# psg-dual-ad9833-simp.net
KiCad netlist of a schematic drawn in EAGLE
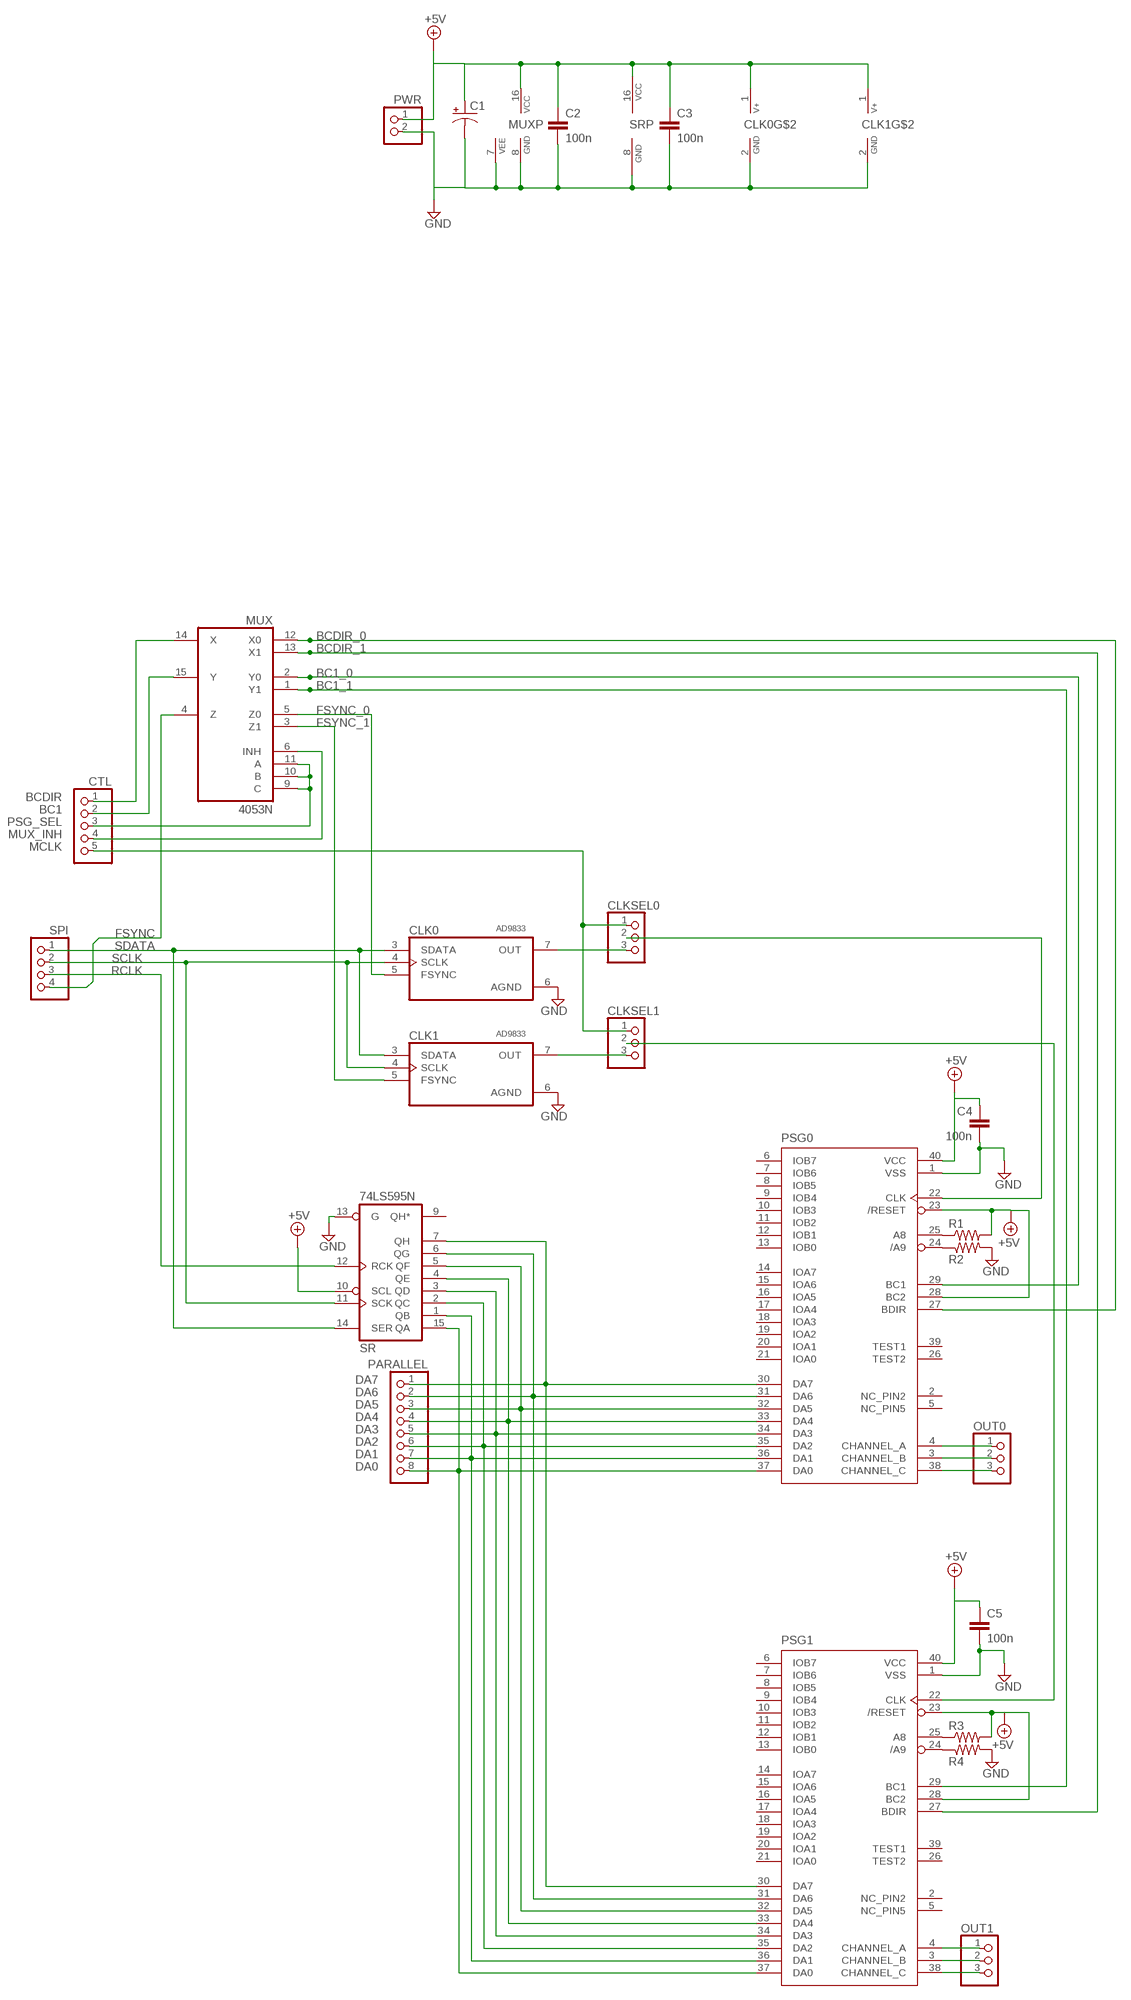
[diagram p0: schematic, sheet 1]

(export (version "E")
  (design (tool "Eeschema 10.0.6"))
  (components
    (comp (ref "C1")
      (value "0501")
      (footprint "eagle-import:050_020_1")
      (libsource (lib "eagle-import") (part "0501"))
    )
    (comp (ref "C2")
      (value "100n")
      (footprint "eagle-import:050X030_025")
      (libsource (lib "eagle-import") (part "050X030_0251"))
    )
    (comp (ref "C3")
      (value "100n")
      (footprint "eagle-import:050X030_025")
      (libsource (lib "eagle-import") (part "050X030_0251"))
    )
    (comp (ref "C4")
      (value "100n")
      (footprint "eagle-import:050X030_025_3")
      (libsource (lib "eagle-import") (part "050X030_0253"))
    )
    (comp (ref "C5")
      (value "100n")
      (footprint "eagle-import:050X030_025_3")
      (libsource (lib "eagle-import") (part "050X030_0253"))
    )
    (comp (ref "CLK0")
      (value "AD9833_MODULE")
      (footprint "eagle-import:AD9833_MODULE")
      (libsource (lib "eagle-import") (part "AD9833_MODULE"))
    )
    (comp (ref "CLK1")
      (value "AD9833_MODULE")
      (footprint "eagle-import:AD9833_MODULE")
      (libsource (lib "eagle-import") (part "AD9833_MODULE"))
    )
    (comp (ref "CLKSEL0")
      (value "PINHD-1X3/90")
      (footprint "eagle-import:1X03_90")
      (libsource (lib "eagle-import") (part "PINHD-1X3/90"))
    )
    (comp (ref "CLKSEL1")
      (value "PINHD-1X3/90")
      (footprint "eagle-import:1X03_90")
      (libsource (lib "eagle-import") (part "PINHD-1X3/90"))
    )
    (comp (ref "CTL")
      (value "PINHD-1X5/90")
      (footprint "eagle-import:1X05_90")
      (libsource (lib "eagle-import") (part "PINHD-1X5/90"))
    )
    (comp (ref "MUX")
      (value "4053N")
      (footprint "eagle-import:DIL16")
      (libsource (lib "eagle-import") (part "4053N"))
    )
    (comp (ref "OUT0")
      (value "PINHD-1X3/90")
      (footprint "eagle-import:1X03_90")
      (libsource (lib "eagle-import") (part "PINHD-1X3/90"))
    )
    (comp (ref "OUT1")
      (value "PINHD-1X3/90")
      (footprint "eagle-import:1X03_90")
      (libsource (lib "eagle-import") (part "PINHD-1X3/90"))
    )
    (comp (ref "PARALLEL")
      (value "PINHD-1X8/90")
      (footprint "eagle-import:1X08_90")
      (libsource (lib "eagle-import") (part "PINHD-1X8/90"))
    )
    (comp (ref "PSG0")
      (value "AY-3-8910")
      (footprint "eagle-import:DIL40")
      (libsource (lib "eagle-import") (part "AY-3-8910"))
    )
    (comp (ref "PSG1")
      (value "AY-3-8910")
      (footprint "eagle-import:DIL40")
      (libsource (lib "eagle-import") (part "AY-3-8910"))
    )
    (comp (ref "PWR")
      (value "PINHD-1X2/90")
      (footprint "eagle-import:1X02_90")
      (libsource (lib "eagle-import") (part "PINHD-1X2/90"))
    )
    (comp (ref "R1")
      (value "6MM.3")
      (footprint "eagle-import:R0207_3")
      (libsource (lib "eagle-import") (part "6MM.3"))
    )
    (comp (ref "R2")
      (value "6MM.3")
      (footprint "eagle-import:R0207_3")
      (libsource (lib "eagle-import") (part "6MM.3"))
    )
    (comp (ref "R3")
      (value "6MM.3")
      (footprint "eagle-import:R0207_3")
      (libsource (lib "eagle-import") (part "6MM.3"))
    )
    (comp (ref "R4")
      (value "6MM.3")
      (footprint "eagle-import:R0207_3")
      (libsource (lib "eagle-import") (part "6MM.3"))
    )
    (comp (ref "SPI")
      (value "PINHD-1X4/90")
      (footprint "eagle-import:1X04_90")
      (libsource (lib "eagle-import") (part "PINHD-1X4/90"))
    )
    (comp (ref "SR")
      (value "74LS595N")
      (footprint "eagle-import:DIL16")
      (libsource (lib "eagle-import") (part "74595NLS"))
    )
  )
  (nets
    (net (code "1") (name "+5V") (class "Default")
      (node (ref "C1") (pin "+") (pinfunction "+_+") (pintype "passive"))
      (node (ref "C2") (pin "1") (pinfunction "1_1") (pintype "passive"))
      (node (ref "C3") (pin "1") (pinfunction "1_1") (pintype "passive"))
      (node (ref "C4") (pin "1") (pinfunction "1_1") (pintype "passive"))
      (node (ref "C5") (pin "1") (pinfunction "1_1") (pintype "passive"))
      (node (ref "CLK0") (pin "1") (pinfunction "+V_1") (pintype "power_in"))
      (node (ref "CLK1") (pin "1") (pinfunction "+V_1") (pintype "power_in"))
      (node (ref "MUX") (pin "16") (pinfunction "VCC_16") (pintype "power_in"))
      (node (ref "PSG0") (pin "23") (pinfunction "/RESET_23") (pintype "input"))
      (node (ref "PSG0") (pin "28") (pinfunction "BC2_28") (pintype "input"))
      (node (ref "PSG0") (pin "40") (pinfunction "VCC_40") (pintype "power_in"))
      (node (ref "PSG1") (pin "23") (pinfunction "/RESET_23") (pintype "input"))
      (node (ref "PSG1") (pin "28") (pinfunction "BC2_28") (pintype "input"))
      (node (ref "PSG1") (pin "40") (pinfunction "VCC_40") (pintype "power_in"))
      (node (ref "PWR") (pin "1") (pinfunction "1_1") (pintype "passive"))
      (node (ref "R1") (pin "2") (pinfunction "2_2") (pintype "passive"))
      (node (ref "R3") (pin "2") (pinfunction "2_2") (pintype "passive"))
      (node (ref "SR") (pin "10") (pinfunction "SCL_10") (pintype "input"))
      (node (ref "SR") (pin "16") (pinfunction "VCC_16") (pintype "power_in"))
    )
    (net (code "2") (name "/BC1") (class "Default")
      (node (ref "CTL") (pin "2") (pinfunction "2_2") (pintype "passive"))
      (node (ref "MUX") (pin "15") (pinfunction "Y_15") (pintype "bidirectional"))
    )
    (net (code "3") (name "/BC1_0") (class "Default")
      (node (ref "MUX") (pin "2") (pinfunction "Y0_2") (pintype "bidirectional"))
      (node (ref "PSG0") (pin "29") (pinfunction "BC1_29") (pintype "input"))
    )
    (net (code "4") (name "/BC1_1") (class "Default")
      (node (ref "MUX") (pin "1") (pinfunction "Y1_1") (pintype "bidirectional"))
      (node (ref "PSG1") (pin "29") (pinfunction "BC1_29") (pintype "input"))
    )
    (net (code "5") (name "/BCDIR") (class "Default")
      (node (ref "CTL") (pin "1") (pinfunction "1_1") (pintype "passive"))
      (node (ref "MUX") (pin "14") (pinfunction "X_14") (pintype "bidirectional"))
    )
    (net (code "6") (name "/BCDIR_0") (class "Default")
      (node (ref "MUX") (pin "12") (pinfunction "X0_12") (pintype "bidirectional"))
      (node (ref "PSG0") (pin "27") (pinfunction "BDIR_27") (pintype "input"))
    )
    (net (code "7") (name "/BCDIR_1") (class "Default")
      (node (ref "MUX") (pin "13") (pinfunction "X1_13") (pintype "bidirectional"))
      (node (ref "PSG1") (pin "27") (pinfunction "BDIR_27") (pintype "input"))
    )
    (net (code "8") (name "/DA0") (class "Default")
      (node (ref "PARALLEL") (pin "8") (pinfunction "8_8") (pintype "passive"))
      (node (ref "PSG0") (pin "37") (pinfunction "DA0_37") (pintype "bidirectional"))
      (node (ref "PSG1") (pin "37") (pinfunction "DA0_37") (pintype "bidirectional"))
      (node (ref "SR") (pin "15") (pinfunction "QA_15") (pintype "tri_state"))
    )
    (net (code "9") (name "/DA1") (class "Default")
      (node (ref "PARALLEL") (pin "7") (pinfunction "7_7") (pintype "passive"))
      (node (ref "PSG0") (pin "36") (pinfunction "DA1_36") (pintype "bidirectional"))
      (node (ref "PSG1") (pin "36") (pinfunction "DA1_36") (pintype "bidirectional"))
      (node (ref "SR") (pin "1") (pinfunction "QB_1") (pintype "tri_state"))
    )
    (net (code "10") (name "/DA2") (class "Default")
      (node (ref "PARALLEL") (pin "6") (pinfunction "6_6") (pintype "passive"))
      (node (ref "PSG0") (pin "35") (pinfunction "DA2_35") (pintype "bidirectional"))
      (node (ref "PSG1") (pin "35") (pinfunction "DA2_35") (pintype "bidirectional"))
      (node (ref "SR") (pin "2") (pinfunction "QC_2") (pintype "tri_state"))
    )
    (net (code "11") (name "/DA3") (class "Default")
      (node (ref "PARALLEL") (pin "5") (pinfunction "5_5") (pintype "passive"))
      (node (ref "PSG0") (pin "34") (pinfunction "DA3_34") (pintype "bidirectional"))
      (node (ref "PSG1") (pin "34") (pinfunction "DA3_34") (pintype "bidirectional"))
      (node (ref "SR") (pin "3") (pinfunction "QD_3") (pintype "tri_state"))
    )
    (net (code "12") (name "/DA4") (class "Default")
      (node (ref "PARALLEL") (pin "4") (pinfunction "4_4") (pintype "passive"))
      (node (ref "PSG0") (pin "33") (pinfunction "DA4_33") (pintype "bidirectional"))
      (node (ref "PSG1") (pin "33") (pinfunction "DA4_33") (pintype "bidirectional"))
      (node (ref "SR") (pin "4") (pinfunction "QE_4") (pintype "tri_state"))
    )
    (net (code "13") (name "/DA5") (class "Default")
      (node (ref "PARALLEL") (pin "3") (pinfunction "3_3") (pintype "passive"))
      (node (ref "PSG0") (pin "32") (pinfunction "DA5_32") (pintype "bidirectional"))
      (node (ref "PSG1") (pin "32") (pinfunction "DA5_32") (pintype "bidirectional"))
      (node (ref "SR") (pin "5") (pinfunction "QF_5") (pintype "tri_state"))
    )
    (net (code "14") (name "/DA6") (class "Default")
      (node (ref "PARALLEL") (pin "2") (pinfunction "2_2") (pintype "passive"))
      (node (ref "PSG0") (pin "31") (pinfunction "DA6_31") (pintype "bidirectional"))
      (node (ref "PSG1") (pin "31") (pinfunction "DA6_31") (pintype "bidirectional"))
      (node (ref "SR") (pin "6") (pinfunction "QG_6") (pintype "tri_state"))
    )
    (net (code "15") (name "/DA7") (class "Default")
      (node (ref "PARALLEL") (pin "1") (pinfunction "1_1") (pintype "passive"))
      (node (ref "PSG0") (pin "30") (pinfunction "DA7_30") (pintype "bidirectional"))
      (node (ref "PSG1") (pin "30") (pinfunction "DA7_30") (pintype "bidirectional"))
      (node (ref "SR") (pin "7") (pinfunction "QH_7") (pintype "tri_state"))
    )
    (net (code "16") (name "/FSYNC") (class "Default")
      (node (ref "MUX") (pin "4") (pinfunction "Z_4") (pintype "bidirectional"))
      (node (ref "SPI") (pin "4") (pinfunction "4_4") (pintype "passive"))
    )
    (net (code "17") (name "/FSYNC_0") (class "Default")
      (node (ref "CLK0") (pin "5") (pinfunction "FSYNC_5") (pintype "input"))
      (node (ref "MUX") (pin "5") (pinfunction "Z0_5") (pintype "bidirectional"))
    )
    (net (code "18") (name "/FSYNC_1") (class "Default")
      (node (ref "CLK1") (pin "5") (pinfunction "FSYNC_5") (pintype "input"))
      (node (ref "MUX") (pin "3") (pinfunction "Z1_3") (pintype "bidirectional"))
    )
    (net (code "19") (name "/MCLK") (class "Default")
      (node (ref "CLKSEL0") (pin "1") (pinfunction "1_1") (pintype "passive"))
      (node (ref "CLKSEL1") (pin "1") (pinfunction "1_1") (pintype "passive"))
      (node (ref "CTL") (pin "5") (pinfunction "5_5") (pintype "passive"))
    )
    (net (code "20") (name "/MUX_INH") (class "Default")
      (node (ref "CTL") (pin "4") (pinfunction "4_4") (pintype "passive"))
      (node (ref "MUX") (pin "6") (pinfunction "INH_6") (pintype "input"))
    )
    (net (code "21") (name "/PSG_SEL") (class "Default")
      (node (ref "CTL") (pin "3") (pinfunction "3_3") (pintype "passive"))
      (node (ref "MUX") (pin "10") (pinfunction "B_10") (pintype "input"))
      (node (ref "MUX") (pin "11") (pinfunction "A_11") (pintype "input"))
      (node (ref "MUX") (pin "9") (pinfunction "C_9") (pintype "input"))
    )
    (net (code "22") (name "/RCLK") (class "Default")
      (node (ref "SPI") (pin "3") (pinfunction "3_3") (pintype "passive"))
      (node (ref "SR") (pin "12") (pinfunction "RCK_12") (pintype "input"))
    )
    (net (code "23") (name "/SCLK") (class "Default")
      (node (ref "CLK0") (pin "4") (pinfunction "SCLK_4") (pintype "input"))
      (node (ref "CLK1") (pin "4") (pinfunction "SCLK_4") (pintype "input"))
      (node (ref "SPI") (pin "2") (pinfunction "2_2") (pintype "passive"))
      (node (ref "SR") (pin "11") (pinfunction "SCK_11") (pintype "input"))
    )
    (net (code "24") (name "/SDATA") (class "Default")
      (node (ref "CLK0") (pin "3") (pinfunction "SDATA_3") (pintype "bidirectional"))
      (node (ref "CLK1") (pin "3") (pinfunction "SDATA_3") (pintype "bidirectional"))
      (node (ref "SPI") (pin "1") (pinfunction "1_1") (pintype "passive"))
      (node (ref "SR") (pin "14") (pinfunction "SER_14") (pintype "input"))
    )
    (net (code "25") (name "GND") (class "Default")
      (node (ref "C1") (pin "-") (pinfunction "-_-") (pintype "passive"))
      (node (ref "C2") (pin "2") (pinfunction "2_2") (pintype "passive"))
      (node (ref "C3") (pin "2") (pinfunction "2_2") (pintype "passive"))
      (node (ref "C4") (pin "2") (pinfunction "2_2") (pintype "passive"))
      (node (ref "C5") (pin "2") (pinfunction "2_2") (pintype "passive"))
      (node (ref "CLK0") (pin "2") (pinfunction "GND_2") (pintype "power_in"))
      (node (ref "CLK0") (pin "6") (pinfunction "AGND_6") (pintype "power_in"))
      (node (ref "CLK1") (pin "2") (pinfunction "GND_2") (pintype "power_in"))
      (node (ref "CLK1") (pin "6") (pinfunction "AGND_6") (pintype "power_in"))
      (node (ref "MUX") (pin "7") (pinfunction "VEE_7") (pintype "power_in"))
      (node (ref "MUX") (pin "8") (pinfunction "GND_8") (pintype "power_in"))
      (node (ref "PSG0") (pin "1") (pinfunction "VSS_1") (pintype "power_in"))
      (node (ref "PSG1") (pin "1") (pinfunction "VSS_1") (pintype "power_in"))
      (node (ref "PWR") (pin "2") (pinfunction "2_2") (pintype "passive"))
      (node (ref "R2") (pin "2") (pinfunction "2_2") (pintype "passive"))
      (node (ref "R4") (pin "2") (pinfunction "2_2") (pintype "passive"))
      (node (ref "SR") (pin "13") (pinfunction "G_13") (pintype "input"))
      (node (ref "SR") (pin "8") (pinfunction "GND_8") (pintype "power_in"))
    )
    (net (code "26") (name "Net-(CLK0A-OUT)") (class "Default")
      (node (ref "CLK0") (pin "7") (pinfunction "OUT_7") (pintype "output"))
      (node (ref "CLKSEL0") (pin "3") (pinfunction "3_3") (pintype "passive"))
    )
    (net (code "27") (name "Net-(CLK1A-OUT)") (class "Default")
      (node (ref "CLK1") (pin "7") (pinfunction "OUT_7") (pintype "output"))
      (node (ref "CLKSEL1") (pin "3") (pinfunction "3_3") (pintype "passive"))
    )
    (net (code "28") (name "Net-(PSG0-A8)") (class "Default")
      (node (ref "PSG0") (pin "25") (pinfunction "A8_25") (pintype "bidirectional"))
      (node (ref "R1") (pin "1") (pinfunction "1_1") (pintype "passive"))
    )
    (net (code "29") (name "Net-(PSG0-CHANNEL_A)") (class "Default")
      (node (ref "OUT0") (pin "1") (pinfunction "1_1") (pintype "passive"))
      (node (ref "PSG0") (pin "4") (pinfunction "CHANNEL_A_4") (pintype "output"))
    )
    (net (code "30") (name "Net-(PSG0-CHANNEL_B)") (class "Default")
      (node (ref "OUT0") (pin "2") (pinfunction "2_2") (pintype "passive"))
      (node (ref "PSG0") (pin "3") (pinfunction "CHANNEL_B_3") (pintype "output"))
    )
    (net (code "31") (name "Net-(PSG0-CHANNEL_C)") (class "Default")
      (node (ref "OUT0") (pin "3") (pinfunction "3_3") (pintype "passive"))
      (node (ref "PSG0") (pin "38") (pinfunction "CHANNEL_C_38") (pintype "output"))
    )
    (net (code "32") (name "Net-(PSG0-CLK)") (class "Default")
      (node (ref "CLKSEL0") (pin "2") (pinfunction "2_2") (pintype "passive"))
      (node (ref "PSG0") (pin "22") (pinfunction "CLK_22") (pintype "input"))
    )
    (net (code "33") (name "Net-(PSG0-{slash}A9)") (class "Default")
      (node (ref "PSG0") (pin "24") (pinfunction "/A9_24") (pintype "bidirectional"))
      (node (ref "R2") (pin "1") (pinfunction "1_1") (pintype "passive"))
    )
    (net (code "34") (name "Net-(PSG1-A8)") (class "Default")
      (node (ref "PSG1") (pin "25") (pinfunction "A8_25") (pintype "bidirectional"))
      (node (ref "R3") (pin "1") (pinfunction "1_1") (pintype "passive"))
    )
    (net (code "35") (name "Net-(PSG1-CHANNEL_A)") (class "Default")
      (node (ref "OUT1") (pin "1") (pinfunction "1_1") (pintype "passive"))
      (node (ref "PSG1") (pin "4") (pinfunction "CHANNEL_A_4") (pintype "output"))
    )
    (net (code "36") (name "Net-(PSG1-CHANNEL_B)") (class "Default")
      (node (ref "OUT1") (pin "2") (pinfunction "2_2") (pintype "passive"))
      (node (ref "PSG1") (pin "3") (pinfunction "CHANNEL_B_3") (pintype "output"))
    )
    (net (code "37") (name "Net-(PSG1-CHANNEL_C)") (class "Default")
      (node (ref "OUT1") (pin "3") (pinfunction "3_3") (pintype "passive"))
      (node (ref "PSG1") (pin "38") (pinfunction "CHANNEL_C_38") (pintype "output"))
    )
    (net (code "38") (name "Net-(PSG1-CLK)") (class "Default")
      (node (ref "CLKSEL1") (pin "2") (pinfunction "2_2") (pintype "passive"))
      (node (ref "PSG1") (pin "22") (pinfunction "CLK_22") (pintype "input"))
    )
    (net (code "39") (name "Net-(PSG1-{slash}A9)") (class "Default")
      (node (ref "PSG1") (pin "24") (pinfunction "/A9_24") (pintype "bidirectional"))
      (node (ref "R4") (pin "1") (pinfunction "1_1") (pintype "passive"))
    )
    (net (code "40") (name "unconnected-(PSG0-IOA0-Pad21)") (class "Default")
      (node (ref "PSG0") (pin "21") (pinfunction "IOA0_21") (pintype "bidirectional"))
    )
    (net (code "41") (name "unconnected-(PSG0-IOA1-Pad20)") (class "Default")
      (node (ref "PSG0") (pin "20") (pinfunction "IOA1_20") (pintype "bidirectional"))
    )
    (net (code "42") (name "unconnected-(PSG0-IOA2-Pad19)") (class "Default")
      (node (ref "PSG0") (pin "19") (pinfunction "IOA2_19") (pintype "bidirectional"))
    )
    (net (code "43") (name "unconnected-(PSG0-IOA3-Pad18)") (class "Default")
      (node (ref "PSG0") (pin "18") (pinfunction "IOA3_18") (pintype "bidirectional"))
    )
    (net (code "44") (name "unconnected-(PSG0-IOA4-Pad17)") (class "Default")
      (node (ref "PSG0") (pin "17") (pinfunction "IOA4_17") (pintype "bidirectional"))
    )
    (net (code "45") (name "unconnected-(PSG0-IOA5-Pad16)") (class "Default")
      (node (ref "PSG0") (pin "16") (pinfunction "IOA5_16") (pintype "bidirectional"))
    )
    (net (code "46") (name "unconnected-(PSG0-IOA6-Pad15)") (class "Default")
      (node (ref "PSG0") (pin "15") (pinfunction "IOA6_15") (pintype "bidirectional"))
    )
    (net (code "47") (name "unconnected-(PSG0-IOA7-Pad14)") (class "Default")
      (node (ref "PSG0") (pin "14") (pinfunction "IOA7_14") (pintype "bidirectional"))
    )
    (net (code "48") (name "unconnected-(PSG0-IOB0-Pad13)") (class "Default")
      (node (ref "PSG0") (pin "13") (pinfunction "IOB0_13") (pintype "bidirectional"))
    )
    (net (code "49") (name "unconnected-(PSG0-IOB1-Pad12)") (class "Default")
      (node (ref "PSG0") (pin "12") (pinfunction "IOB1_12") (pintype "bidirectional"))
    )
    (net (code "50") (name "unconnected-(PSG0-IOB2-Pad11)") (class "Default")
      (node (ref "PSG0") (pin "11") (pinfunction "IOB2_11") (pintype "bidirectional"))
    )
    (net (code "51") (name "unconnected-(PSG0-IOB3-Pad10)") (class "Default")
      (node (ref "PSG0") (pin "10") (pinfunction "IOB3_10") (pintype "bidirectional"))
    )
    (net (code "52") (name "unconnected-(PSG0-IOB4-Pad9)") (class "Default")
      (node (ref "PSG0") (pin "9") (pinfunction "IOB4_9") (pintype "bidirectional"))
    )
    (net (code "53") (name "unconnected-(PSG0-IOB5-Pad8)") (class "Default")
      (node (ref "PSG0") (pin "8") (pinfunction "IOB5_8") (pintype "bidirectional"))
    )
    (net (code "54") (name "unconnected-(PSG0-IOB6-Pad7)") (class "Default")
      (node (ref "PSG0") (pin "7") (pinfunction "IOB6_7") (pintype "bidirectional"))
    )
    (net (code "55") (name "unconnected-(PSG0-IOB7-Pad6)") (class "Default")
      (node (ref "PSG0") (pin "6") (pinfunction "IOB7_6") (pintype "bidirectional"))
    )
    (net (code "56") (name "unconnected-(PSG0-NC_PIN2-Pad2)") (class "Default")
      (node (ref "PSG0") (pin "2") (pinfunction "NC_PIN2_2") (pintype "no_connect"))
    )
    (net (code "57") (name "unconnected-(PSG0-NC_PIN5-Pad5)") (class "Default")
      (node (ref "PSG0") (pin "5") (pinfunction "NC_PIN5_5") (pintype "bidirectional"))
    )
    (net (code "58") (name "unconnected-(PSG0-TEST1-Pad39)") (class "Default")
      (node (ref "PSG0") (pin "39") (pinfunction "TEST1_39") (pintype "no_connect"))
    )
    (net (code "59") (name "unconnected-(PSG0-TEST2-Pad26)") (class "Default")
      (node (ref "PSG0") (pin "26") (pinfunction "TEST2_26") (pintype "no_connect"))
    )
    (net (code "60") (name "unconnected-(PSG1-IOA0-Pad21)") (class "Default")
      (node (ref "PSG1") (pin "21") (pinfunction "IOA0_21") (pintype "bidirectional"))
    )
    (net (code "61") (name "unconnected-(PSG1-IOA1-Pad20)") (class "Default")
      (node (ref "PSG1") (pin "20") (pinfunction "IOA1_20") (pintype "bidirectional"))
    )
    (net (code "62") (name "unconnected-(PSG1-IOA2-Pad19)") (class "Default")
      (node (ref "PSG1") (pin "19") (pinfunction "IOA2_19") (pintype "bidirectional"))
    )
    (net (code "63") (name "unconnected-(PSG1-IOA3-Pad18)") (class "Default")
      (node (ref "PSG1") (pin "18") (pinfunction "IOA3_18") (pintype "bidirectional"))
    )
    (net (code "64") (name "unconnected-(PSG1-IOA4-Pad17)") (class "Default")
      (node (ref "PSG1") (pin "17") (pinfunction "IOA4_17") (pintype "bidirectional"))
    )
    (net (code "65") (name "unconnected-(PSG1-IOA5-Pad16)") (class "Default")
      (node (ref "PSG1") (pin "16") (pinfunction "IOA5_16") (pintype "bidirectional"))
    )
    (net (code "66") (name "unconnected-(PSG1-IOA6-Pad15)") (class "Default")
      (node (ref "PSG1") (pin "15") (pinfunction "IOA6_15") (pintype "bidirectional"))
    )
    (net (code "67") (name "unconnected-(PSG1-IOA7-Pad14)") (class "Default")
      (node (ref "PSG1") (pin "14") (pinfunction "IOA7_14") (pintype "bidirectional"))
    )
    (net (code "68") (name "unconnected-(PSG1-IOB0-Pad13)") (class "Default")
      (node (ref "PSG1") (pin "13") (pinfunction "IOB0_13") (pintype "bidirectional"))
    )
    (net (code "69") (name "unconnected-(PSG1-IOB1-Pad12)") (class "Default")
      (node (ref "PSG1") (pin "12") (pinfunction "IOB1_12") (pintype "bidirectional"))
    )
    (net (code "70") (name "unconnected-(PSG1-IOB2-Pad11)") (class "Default")
      (node (ref "PSG1") (pin "11") (pinfunction "IOB2_11") (pintype "bidirectional"))
    )
    (net (code "71") (name "unconnected-(PSG1-IOB3-Pad10)") (class "Default")
      (node (ref "PSG1") (pin "10") (pinfunction "IOB3_10") (pintype "bidirectional"))
    )
    (net (code "72") (name "unconnected-(PSG1-IOB4-Pad9)") (class "Default")
      (node (ref "PSG1") (pin "9") (pinfunction "IOB4_9") (pintype "bidirectional"))
    )
    (net (code "73") (name "unconnected-(PSG1-IOB5-Pad8)") (class "Default")
      (node (ref "PSG1") (pin "8") (pinfunction "IOB5_8") (pintype "bidirectional"))
    )
    (net (code "74") (name "unconnected-(PSG1-IOB6-Pad7)") (class "Default")
      (node (ref "PSG1") (pin "7") (pinfunction "IOB6_7") (pintype "bidirectional"))
    )
    (net (code "75") (name "unconnected-(PSG1-IOB7-Pad6)") (class "Default")
      (node (ref "PSG1") (pin "6") (pinfunction "IOB7_6") (pintype "bidirectional"))
    )
    (net (code "76") (name "unconnected-(PSG1-NC_PIN2-Pad2)") (class "Default")
      (node (ref "PSG1") (pin "2") (pinfunction "NC_PIN2_2") (pintype "no_connect"))
    )
    (net (code "77") (name "unconnected-(PSG1-NC_PIN5-Pad5)") (class "Default")
      (node (ref "PSG1") (pin "5") (pinfunction "NC_PIN5_5") (pintype "bidirectional"))
    )
    (net (code "78") (name "unconnected-(PSG1-TEST1-Pad39)") (class "Default")
      (node (ref "PSG1") (pin "39") (pinfunction "TEST1_39") (pintype "no_connect"))
    )
    (net (code "79") (name "unconnected-(PSG1-TEST2-Pad26)") (class "Default")
      (node (ref "PSG1") (pin "26") (pinfunction "TEST2_26") (pintype "no_connect"))
    )
    (net (code "80") (name "unconnected-(SRA-QH*-Pad9)") (class "Default")
      (node (ref "SR") (pin "9") (pinfunction "QH*_9") (pintype "tri_state"))
    )
  )
)
